# Sheet4.net
KiCad netlist of a schematic drawn in Altium Designer
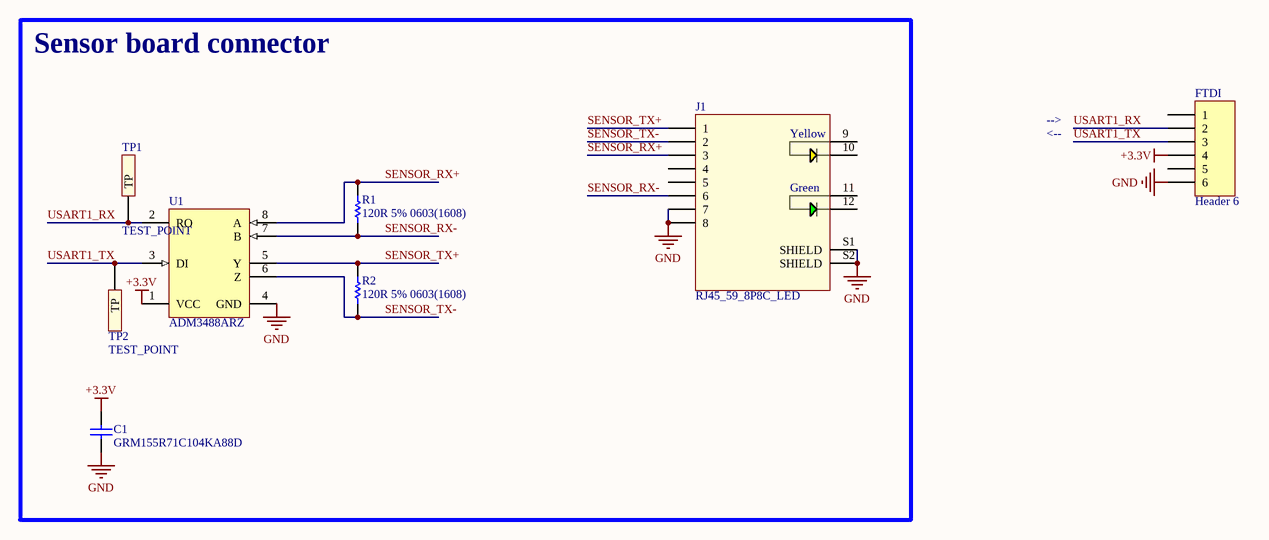
[diagram p0: Sheet4.SchDoc]

(export (version "E")
  (design (tool "Eeschema 10.0.6"))
  (components
    (comp (ref "C1")
      (value "GRM155R71C104KA88D")
      (footprint "CAPC1005X55X25ML05T10")
      (description "Chip Capacitor, 0.1 uF, +/- 10%, 16 V, -55 to 125 degC, 0402 (1005 Metric), RoHS, Tape and Reel")
      (fields (field (name "VOLTAGE") "16V") (field (name "TOLERANCE") "10%"))
      (libsource (lib "Altium Content Vault") (part "CAP-NP-2"))
    )
    (comp (ref "FTDI")
      (value "Header 6")
      (footprint "HDR1X6")
      (description "Header, 6-Pin")
      (fields (field (name "PUBLISHER") "Altium Limited"))
      (libsource (lib "Miscellaneous Connectors") (part "Header 6"))
    )
    (comp (ref "J1")
      (value "RJ45_59_8P8C_LED")
      (footprint "RJ45_59_8P8C_LED")
      (description "Generic RJ49 jack with LED and without magnetics")
      (fields (field (name "MANUFACTURER") "Unknown/Generic"))
      (libsource (lib "Blinkinlabs") (part "RJ45_59_8P8C_LED"))
    )
    (comp (ref "R1")
      (value "120R 5% 0603(1608)")
      (footprint "RESC0603(1608)_L")
      (description "120R 0.1W 5% 0603 (1608 Metric)  SMD")
      (fields (field (name "POWER") "0.1 W") (field (name "TOLERANCE") "5 %"))
      (libsource (lib "Altium Content Vault") (part "RES"))
    )
    (comp (ref "R2")
      (value "120R 5% 0603(1608)")
      (footprint "RESC0603(1608)_L")
      (description "120R 0.1W 5% 0603 (1608 Metric)  SMD")
      (fields (field (name "POWER") "0.1 W") (field (name "TOLERANCE") "5 %"))
      (libsource (lib "Altium Content Vault") (part "RES"))
    )
    (comp (ref "TP1")
      (value "TEST_POINT")
      (footprint "TP-SMD-1mm")
      (description "Test point")
      (libsource (lib "") (part "TEST_POINT_1"))
    )
    (comp (ref "TP2")
      (value "TEST_POINT")
      (footprint "TP-SMD-1mm")
      (description "Test point")
      (libsource (lib "Blinkinlabs") (part "TEST_POINT"))
    )
    (comp (ref "U1")
      (value "ADM3488ARZ")
      (footprint "ADI-R-8_L")
      (fields (field (name "MANUFACTURER") "Analog Devices"))
      (libsource (lib "Altium Content Vault") (part "ADI-ADM3488_90-R-8"))
    )
  )
  (nets
    (net (code "1") (name "+3.3V") (class "Default")
      (node (ref "C1") (pin "2") (pinfunction "2_2") (pintype "passive"))
      (node (ref "FTDI") (pin "4") (pinfunction "4_4") (pintype "passive"))
      (node (ref "U1") (pin "1") (pinfunction "VCC_1") (pintype "power_in"))
    )
    (net (code "2") (name "/SENSOR_RX+") (class "Default")
      (node (ref "J1") (pin "3") (pinfunction "3_3") (pintype "passive"))
      (node (ref "R1") (pin "2") (pinfunction "2_2") (pintype "passive"))
      (node (ref "U1") (pin "8") (pinfunction "A_8") (pintype "input"))
    )
    (net (code "3") (name "/SENSOR_RX-") (class "Default")
      (node (ref "J1") (pin "6") (pinfunction "6_6") (pintype "passive"))
      (node (ref "R1") (pin "1") (pinfunction "1_1") (pintype "passive"))
      (node (ref "U1") (pin "7") (pinfunction "B_7") (pintype "input"))
    )
    (net (code "4") (name "/SENSOR_TX+") (class "Default")
      (node (ref "J1") (pin "1") (pinfunction "1_1") (pintype "passive"))
      (node (ref "R2") (pin "2") (pinfunction "2_2") (pintype "passive"))
      (node (ref "U1") (pin "5") (pinfunction "Y_5") (pintype "tri_state"))
    )
    (net (code "5") (name "/SENSOR_TX-") (class "Default")
      (node (ref "J1") (pin "2") (pinfunction "2_2") (pintype "passive"))
      (node (ref "R2") (pin "1") (pinfunction "1_1") (pintype "passive"))
      (node (ref "U1") (pin "6") (pinfunction "Z_6") (pintype "tri_state"))
    )
    (net (code "6") (name "/USART1_RX") (class "Default")
      (node (ref "FTDI") (pin "2") (pinfunction "2_2") (pintype "passive"))
      (node (ref "TP1") (pin "1") (pinfunction "TP_1") (pintype "passive"))
      (node (ref "U1") (pin "2") (pinfunction "RO_2") (pintype "tri_state"))
    )
    (net (code "7") (name "/USART1_TX") (class "Default")
      (node (ref "FTDI") (pin "3") (pinfunction "3_3") (pintype "passive"))
      (node (ref "TP2") (pin "1") (pinfunction "TP_1") (pintype "passive"))
      (node (ref "U1") (pin "3") (pinfunction "DI_3") (pintype "input"))
    )
    (net (code "8") (name "GND") (class "Default")
      (node (ref "C1") (pin "1") (pinfunction "1_1") (pintype "passive"))
      (node (ref "FTDI") (pin "6") (pinfunction "6_6") (pintype "passive"))
      (node (ref "J1") (pin "7") (pinfunction "7_7") (pintype "passive"))
      (node (ref "J1") (pin "8") (pinfunction "8_8") (pintype "passive"))
      (node (ref "J1") (pin "S1") (pinfunction "SHIELD_S1") (pintype "passive"))
      (node (ref "J1") (pin "S2") (pinfunction "SHIELD_S2") (pintype "passive"))
      (node (ref "U1") (pin "4") (pinfunction "GND_4") (pintype "power_in"))
    )
    (net (code "9") (name "unconnected-(FTDI-Pad1)") (class "Default")
      (node (ref "FTDI") (pin "1") (pinfunction "1_1") (pintype "passive"))
    )
    (net (code "10") (name "unconnected-(FTDI-Pad5)") (class "Default")
      (node (ref "FTDI") (pin "5") (pinfunction "5_5") (pintype "passive"))
    )
    (net (code "11") (name "unconnected-(J1-Green_Anode-Pad11)") (class "Default")
      (node (ref "J1") (pin "11") (pinfunction "Green_Anode_11") (pintype "passive"))
    )
    (net (code "12") (name "unconnected-(J1-Green_Cathode-Pad12)") (class "Default")
      (node (ref "J1") (pin "12") (pinfunction "Green_Cathode_12") (pintype "passive"))
    )
    (net (code "13") (name "unconnected-(J1-Pad4)") (class "Default")
      (node (ref "J1") (pin "4") (pinfunction "4_4") (pintype "passive"))
    )
    (net (code "14") (name "unconnected-(J1-Pad5)") (class "Default")
      (node (ref "J1") (pin "5") (pinfunction "5_5") (pintype "passive"))
    )
    (net (code "15") (name "unconnected-(J1-Yellow_Anode-Pad9)") (class "Default")
      (node (ref "J1") (pin "9") (pinfunction "Yellow_Anode_9") (pintype "passive"))
    )
    (net (code "16") (name "unconnected-(J1-Yellow_Cathode-Pad10)") (class "Default")
      (node (ref "J1") (pin "10") (pinfunction "Yellow_Cathode_10") (pintype "passive"))
    )
  )
)
